# MCU64.net
KiCad netlist of a schematic drawn in Altium Designer
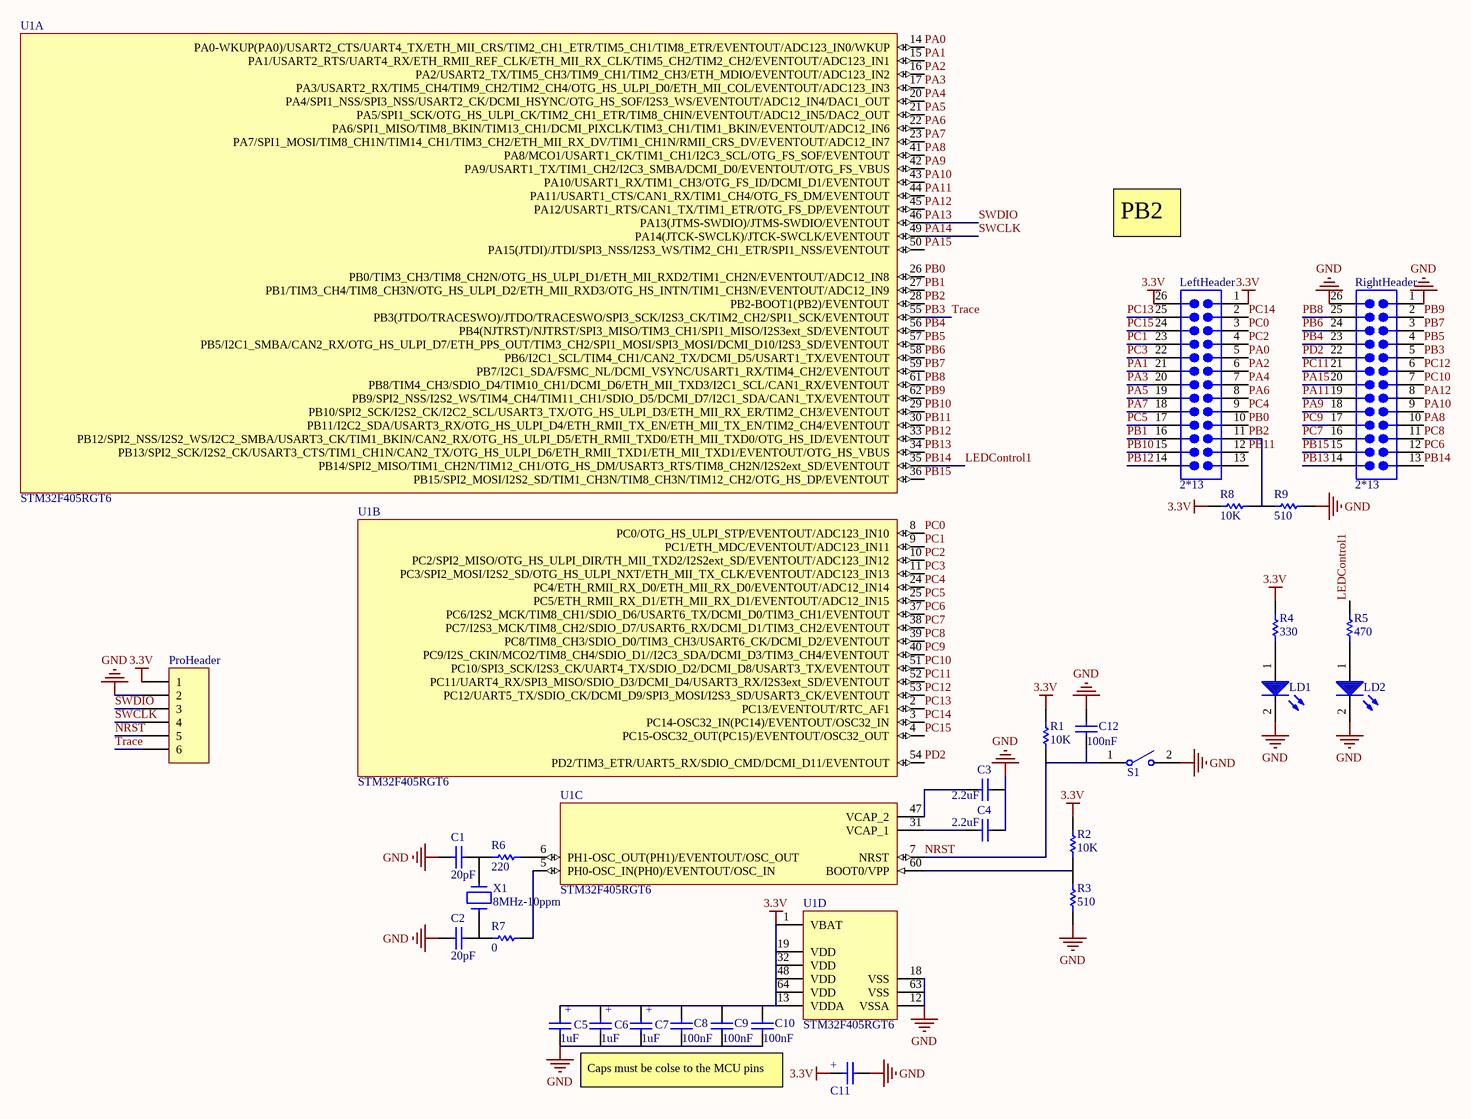
[diagram p0: MCU64.SchDoc]

(export (version "E")
  (design (tool "Eeschema 10.0.6"))
  (components
    (comp (ref "C1")
      (value "20pF")
      (footprint "SMD 805 CAP")
      (libsource (lib "Aryalib") (part "CAP without Pole"))
    )
    (comp (ref "C2")
      (value "20pF")
      (footprint "SMD 805 CAP")
      (libsource (lib "Aryalib") (part "CAP without Pole"))
    )
    (comp (ref "C3")
      (value "2.2uF")
      (footprint "SMD 805 CAP")
      (libsource (lib "Aryalib") (part "CAP without Pole"))
    )
    (comp (ref "C4")
      (value "2.2uF")
      (footprint "SMD 805 CAP")
      (libsource (lib "Aryalib") (part "CAP without Pole"))
    )
    (comp (ref "C5")
      (value "1uF")
      (footprint "MY_CAP_SMD-A")
      (description "3.2X1.6MM")
      (libsource (lib "AMINLIB") (part "CAP_TANTAL_A"))
    )
    (comp (ref "C6")
      (value "1uF")
      (footprint "MY_CAP_SMD-A")
      (description "3.2X1.6MM")
      (libsource (lib "AMINLIB") (part "CAP_TANTAL_A"))
    )
    (comp (ref "C7")
      (value "1uF")
      (footprint "MY_CAP_SMD-A")
      (description "3.2X1.6MM")
      (libsource (lib "AMINLIB") (part "CAP_TANTAL_A"))
    )
    (comp (ref "C8")
      (value "100nF")
      (footprint "SMD 805 CAP")
      (libsource (lib "Aryalib") (part "CAP without Pole"))
    )
    (comp (ref "C9")
      (value "100nF")
      (footprint "SMD 805 CAP")
      (libsource (lib "Aryalib") (part "CAP without Pole"))
    )
    (comp (ref "C10")
      (value "100nF")
      (footprint "SMD 805 CAP")
      (libsource (lib "Aryalib") (part "CAP without Pole"))
    )
    (comp (ref "C11")
      (value "Cap")
      (footprint "MY_CAP_SMD-D")
      (description "7.3X4.3MM")
      (libsource (lib "AMINLIB") (part "CAP_TANTAL_D"))
    )
    (comp (ref "C12")
      (value "100nF")
      (footprint "SMD 805 CAP")
      (libsource (lib "Aryalib") (part "CAP without Pole"))
    )
    (comp (ref "LD1")
      (value "150080BS75000")
      (footprint "LED_0805_Blue")
      (description "SMD mono-color Chip LED, WL-SMCW, Blue")
      (fields
        (field (name "MANUFACTURER") "W黵th Elektronik eiSos GmbH")
        (field (name "CREATED BY") "Christin Otto")
      )
      (libsource (lib "WL-SMCW_rev15b") (part "WL-SMCW 0805  150080BS75000"))
    )
    (comp (ref "LD2")
      (value "150080BS75000")
      (footprint "LED_0805_Blue")
      (description "SMD mono-color Chip LED, WL-SMCW, Blue")
      (fields
        (field (name "MANUFACTURER") "W黵th Elektronik eiSos GmbH")
        (field (name "CREATED BY") "Christin Otto")
      )
      (libsource (lib "WL-SMCW_rev15b") (part "WL-SMCW 0805  150080BS75000"))
    )
    (comp (ref "LeftHeader")
      (value "2*13")
      (footprint "61302621121")
      (description "WR-PHD 2.54 mm Dual Pin Header")
      (fields
        (field (name "MANUFACTURER") "Würth Elektronik eiSos GmbH")
        (field (name "PARTNO") "61302621121")
        (field (name "CREATED BY") "Karrer Zheng")
      )
      (libsource (lib "WE_WR-PHD_Pin Header_2.54mm_rev15c") (part "WE-2.54 mm Pin Header & Jumper 61302621121"))
    )
    (comp (ref "ProHeader")
      (value "WE-2.54 mm Pin Header & Jumper 61300611121")
      (footprint "61300611121")
      (description "WR-PHD 2.54mm Pin Header")
      (fields
        (field (name "MANUFACTURER") "Würth Elektronik eiSos GmbH")
        (field (name "PARTNO") "61300611121")
        (field (name "CREATED BY") "Karrer Zheng")
      )
      (libsource (lib "WE_WR-PHD_Pin Header_2.54mm_rev15c") (part "WE-2.54 mm Pin Header & Jumper 61300611121"))
    )
    (comp (ref "R1") (value "10K") (footprint "SMD 805") (libsource (lib "Aryalib") (part "Resistor")))
    (comp (ref "R2") (value "10K") (footprint "SMD 805") (libsource (lib "Aryalib") (part "Resistor")))
    (comp (ref "R3") (value "510") (footprint "SMD 805") (libsource (lib "Aryalib") (part "Resistor")))
    (comp (ref "R4") (value "330") (footprint "SMD 805") (libsource (lib "Aryalib") (part "Resistor")))
    (comp (ref "R5") (value "470") (footprint "SMD 805") (libsource (lib "Aryalib") (part "Resistor")))
    (comp (ref "R6") (value "220") (footprint "SMD 805") (libsource (lib "Aryalib") (part "Resistor")))
    (comp (ref "R7") (value "0") (footprint "SMD 805") (libsource (lib "Aryalib") (part "Resistor")))
    (comp (ref "R8") (value "10K") (footprint "SMD 805") (libsource (lib "Aryalib") (part "Resistor")))
    (comp (ref "R9") (value "510") (footprint "SMD 805") (libsource (lib "Aryalib") (part "Resistor")))
    (comp (ref "RightHeader")
      (value "2*13")
      (footprint "61302621121")
      (description "WR-PHD 2.54 mm Dual Pin Header")
      (fields
        (field (name "MANUFACTURER") "Würth Elektronik eiSos GmbH")
        (field (name "PARTNO") "61302621121")
        (field (name "CREATED BY") "Karrer Zheng")
      )
      (libsource (lib "WE_WR-PHD_Pin Header_2.54mm_rev15c") (part "WE-2.54 mm Pin Header & Jumper 61302621121"))
    )
    (comp (ref "S1")
      (value "Tact Switch")
      (footprint "4341x10438x6")
      (description "WS-TASV 6.0x3.5 mm SMD")
      (fields
        (field (name "PARTNO") "434111043826")
        (field (name "MANUFACTURER") "Wurth Elektronik")
        (field (name "CREATED BY") "Baojun Chen")
      )
      (libsource (lib "WS-TASV_rev15a") (part "WS-TASV, 434111043826"))
    )
    (comp (ref "U1")
      (value "STM32F405RGT6")
      (footprint "TQFP64_V")
      (libsource (lib "") (part "STM32F405RGT6_1"))
    )
    (comp (ref "X1")
      (value "8MHz-10ppm")
      (footprint "My_Crystal")
      (description "Crystal")
      (libsource (lib "AMINLIB") (part "CRYSTAL"))
    )
  )
  (nets
    (net (code "1") (name "/LEDControl1") (class "Default")
      (node (ref "R5") (pin "2") (pinfunction "2_2") (pintype "passive"))
      (node (ref "RightHeader") (pin "13") (pinfunction "13_13") (pintype "passive"))
      (node (ref "U1") (pin "35") (pinfunction "PB14/SPI2_MISO/TIM1_CH2N/TIM12_CH1/OTG_HS_DM/USART3_RTS/TIM8_CH2N/I2S2ext_SD/EVENTOUT_35") (pintype "bidirectional"))
    )
    (net (code "2") (name "/NRST") (class "Default")
      (node (ref "C12") (pin "1") (pinfunction "1_1") (pintype "passive"))
      (node (ref "ProHeader") (pin "5") (pinfunction "5_5") (pintype "passive"))
      (node (ref "R1") (pin "1") (pinfunction "1_1") (pintype "passive"))
      (node (ref "S1") (pin "1") (pinfunction "1_1") (pintype "passive"))
      (node (ref "U1") (pin "7") (pinfunction "NRST_7") (pintype "bidirectional"))
    )
    (net (code "3") (name "/PA0") (class "Default")
      (node (ref "LeftHeader") (pin "5") (pinfunction "5_5") (pintype "passive"))
      (node (ref "U1") (pin "14") (pinfunction "PA0-WKUP(PA0)/USART2_CTS/UART4_TX/ETH_MII_CRS/TIM2_CH1_ETR/TIM5_CH1/TIM8_ETR/EVENTOUT/ADC123_IN0/WKUP_14") (pintype "bidirectional"))
    )
    (net (code "4") (name "/PA1") (class "Default")
      (node (ref "LeftHeader") (pin "21") (pinfunction "21_21") (pintype "passive"))
      (node (ref "U1") (pin "15") (pinfunction "PA1/USART2_RTS/UART4_RX/ETH_RMII_REF_CLK/ETH_MII_RX_CLK/TIM5_CH2/TIM2_CH2/EVENTOUT/ADC123_IN1_15") (pintype "bidirectional"))
    )
    (net (code "5") (name "/PA2") (class "Default")
      (node (ref "LeftHeader") (pin "6") (pinfunction "6_6") (pintype "passive"))
      (node (ref "U1") (pin "16") (pinfunction "PA2/USART2_TX/TIM5_CH3/TIM9_CH1/TIM2_CH3/ETH_MDIO/EVENTOUT/ADC123_IN2_16") (pintype "bidirectional"))
    )
    (net (code "6") (name "/PA3") (class "Default")
      (node (ref "LeftHeader") (pin "20") (pinfunction "20_20") (pintype "passive"))
      (node (ref "U1") (pin "17") (pinfunction "PA3/USART2_RX/TIM5_CH4/TIM9_CH2/TIM2_CH4/OTG_HS_ULPI_D0/ETH_MII_COL/EVENTOUT/ADC123_IN3_17") (pintype "bidirectional"))
    )
    (net (code "7") (name "/PA4") (class "Default")
      (node (ref "LeftHeader") (pin "7") (pinfunction "7_7") (pintype "passive"))
      (node (ref "U1") (pin "20") (pinfunction "PA4/SPI1_NSS/SPI3_NSS/USART2_CK/DCMI_HSYNC/OTG_HS_SOF/I2S3_WS/EVENTOUT/ADC12_IN4/DAC1_OUT_20") (pintype "bidirectional"))
    )
    (net (code "8") (name "/PA5") (class "Default")
      (node (ref "LeftHeader") (pin "19") (pinfunction "19_19") (pintype "passive"))
      (node (ref "U1") (pin "21") (pinfunction "PA5/SPI1_SCK/OTG_HS_ULPI_CK/TIM2_CH1_ETR/TIM8_CHIN/EVENTOUT/ADC12_IN5/DAC2_OUT_21") (pintype "bidirectional"))
    )
    (net (code "9") (name "/PA6") (class "Default")
      (node (ref "LeftHeader") (pin "8") (pinfunction "8_8") (pintype "passive"))
      (node (ref "U1") (pin "22") (pinfunction "PA6/SPI1_MISO/TIM8_BKIN/TIM13_CH1/DCMI_PIXCLK/TIM3_CH1/TIM1_BKIN/EVENTOUT/ADC12_IN6_22") (pintype "bidirectional"))
    )
    (net (code "10") (name "/PA7") (class "Default")
      (node (ref "LeftHeader") (pin "18") (pinfunction "18_18") (pintype "passive"))
      (node (ref "U1") (pin "23") (pinfunction "PA7/SPI1_MOSI/TIM8_CH1N/TIM14_CH1/TIM3_CH2/ETH_MII_RX_DV/TIM1_CH1N/RMII_CRS_DV/EVENTOUT/ADC12_IN7_23") (pintype "bidirectional"))
    )
    (net (code "11") (name "/PA8") (class "Default")
      (node (ref "RightHeader") (pin "10") (pinfunction "10_10") (pintype "passive"))
      (node (ref "U1") (pin "41") (pinfunction "PA8/MCO1/USART1_CK/TIM1_CH1/I2C3_SCL/OTG_FS_SOF/EVENTOUT_41") (pintype "bidirectional"))
    )
    (net (code "12") (name "/PA9") (class "Default")
      (node (ref "RightHeader") (pin "18") (pinfunction "18_18") (pintype "passive"))
      (node (ref "U1") (pin "42") (pinfunction "PA9/USART1_TX/TIM1_CH2/I2C3_SMBA/DCMI_D0/EVENTOUT/OTG_FS_VBUS_42") (pintype "bidirectional"))
    )
    (net (code "13") (name "/PA10") (class "Default")
      (node (ref "RightHeader") (pin "9") (pinfunction "9_9") (pintype "passive"))
      (node (ref "U1") (pin "43") (pinfunction "PA10/USART1_RX/TIM1_CH3/OTG_FS_ID/DCMI_D1/EVENTOUT_43") (pintype "bidirectional"))
    )
    (net (code "14") (name "/PA11") (class "Default")
      (node (ref "RightHeader") (pin "19") (pinfunction "19_19") (pintype "passive"))
      (node (ref "U1") (pin "44") (pinfunction "PA11/USART1_CTS/CAN1_RX/TIM1_CH4/OTG_FS_DM/EVENTOUT_44") (pintype "bidirectional"))
    )
    (net (code "15") (name "/PA12") (class "Default")
      (node (ref "RightHeader") (pin "8") (pinfunction "8_8") (pintype "passive"))
      (node (ref "U1") (pin "45") (pinfunction "PA12/USART1_RTS/CAN1_TX/TIM1_ETR/OTG_FS_DP/EVENTOUT_45") (pintype "bidirectional"))
    )
    (net (code "16") (name "/PA13") (class "Default")
      (node (ref "ProHeader") (pin "3") (pinfunction "3_3") (pintype "passive"))
      (node (ref "U1") (pin "46") (pinfunction "PA13(JTMS-SWDIO)/JTMS-SWDIO/EVENTOUT_46") (pintype "bidirectional"))
    )
    (net (code "17") (name "/PA14") (class "Default")
      (node (ref "ProHeader") (pin "4") (pinfunction "4_4") (pintype "passive"))
      (node (ref "U1") (pin "49") (pinfunction "PA14(JTCK-SWCLK)/JTCK-SWCLK/EVENTOUT_49") (pintype "bidirectional"))
    )
    (net (code "18") (name "/PA15") (class "Default")
      (node (ref "RightHeader") (pin "20") (pinfunction "20_20") (pintype "passive"))
      (node (ref "U1") (pin "50") (pinfunction "PA15(JTDI)/JTDI/SPI3_NSS/I2S3_WS/TIM2_CH1_ETR/SPI1_NSS/EVENTOUT_50") (pintype "bidirectional"))
    )
    (net (code "19") (name "/PB0") (class "Default")
      (node (ref "LeftHeader") (pin "10") (pinfunction "10_10") (pintype "passive"))
      (node (ref "U1") (pin "26") (pinfunction "PB0/TIM3_CH3/TIM8_CH2N/OTG_HS_ULPI_D1/ETH_MII_RXD2/TIM1_CH2N/EVENTOUT/ADC12_IN8_26") (pintype "bidirectional"))
    )
    (net (code "20") (name "/PB1") (class "Default")
      (node (ref "LeftHeader") (pin "16") (pinfunction "16_16") (pintype "passive"))
      (node (ref "U1") (pin "27") (pinfunction "PB1/TIM3_CH4/TIM8_CH3N/OTG_HS_ULPI_D2/ETH_MII_RXD3/OTG_HS_INTN/TIM1_CH3N/EVENTOUT/ADC12_IN9_27") (pintype "bidirectional"))
    )
    (net (code "21") (name "/PB2") (class "Default")
      (node (ref "LeftHeader") (pin "11") (pinfunction "11_11") (pintype "passive"))
      (node (ref "R8") (pin "1") (pinfunction "1_1") (pintype "passive"))
      (node (ref "R9") (pin "2") (pinfunction "2_2") (pintype "passive"))
      (node (ref "U1") (pin "28") (pinfunction "PB2-BOOT1(PB2)/EVENTOUT_28") (pintype "bidirectional"))
    )
    (net (code "22") (name "/PB3") (class "Default")
      (node (ref "ProHeader") (pin "6") (pinfunction "6_6") (pintype "passive"))
      (node (ref "RightHeader") (pin "5") (pinfunction "5_5") (pintype "passive"))
      (node (ref "U1") (pin "55") (pinfunction "PB3(JTDO/TRACESWO)/JTDO/TRACESWO/SPI3_SCK/I2S3_CK/TIM2_CH2/SPI1_SCK/EVENTOUT_55") (pintype "bidirectional"))
    )
    (net (code "23") (name "/PB4") (class "Default")
      (node (ref "RightHeader") (pin "23") (pinfunction "23_23") (pintype "passive"))
      (node (ref "U1") (pin "56") (pinfunction "PB4(NJTRST)/NJTRST/SPI3_MISO/TIM3_CH1/SPI1_MISO/I2S3ext_SD/EVENTOUT_56") (pintype "bidirectional"))
    )
    (net (code "24") (name "/PB5") (class "Default")
      (node (ref "RightHeader") (pin "4") (pinfunction "4_4") (pintype "passive"))
      (node (ref "U1") (pin "57") (pinfunction "PB5/I2C1_SMBA/CAN2_RX/OTG_HS_ULPI_D7/ETH_PPS_OUT/TIM3_CH2/SPI1_MOSI/SPI3_MOSI/DCMI_D10/I2S3_SD/EVENTOUT_57") (pintype "bidirectional"))
    )
    (net (code "25") (name "/PB6") (class "Default")
      (node (ref "RightHeader") (pin "24") (pinfunction "24_24") (pintype "passive"))
      (node (ref "U1") (pin "58") (pinfunction "PB6/I2C1_SCL/TIM4_CH1/CAN2_TX/DCMI_D5/USART1_TX/EVENTOUT_58") (pintype "bidirectional"))
    )
    (net (code "26") (name "/PB7") (class "Default")
      (node (ref "RightHeader") (pin "3") (pinfunction "3_3") (pintype "passive"))
      (node (ref "U1") (pin "59") (pinfunction "PB7/I2C1_SDA/FSMC_NL/DCMI_VSYNC/USART1_RX/TIM4_CH2/EVENTOUT_59") (pintype "bidirectional"))
    )
    (net (code "27") (name "/PB8") (class "Default")
      (node (ref "RightHeader") (pin "25") (pinfunction "25_25") (pintype "passive"))
      (node (ref "U1") (pin "61") (pinfunction "PB8/TIM4_CH3/SDIO_D4/TIM10_CH1/DCMI_D6/ETH_MII_TXD3/I2C1_SCL/CAN1_RX/EVENTOUT_61") (pintype "bidirectional"))
    )
    (net (code "28") (name "/PB9") (class "Default")
      (node (ref "RightHeader") (pin "2") (pinfunction "2_2") (pintype "passive"))
      (node (ref "U1") (pin "62") (pinfunction "PB9/SPI2_NSS/I2S2_WS/TIM4_CH4/TIM11_CH1/SDIO_D5/DCMI_D7/I2C1_SDA/CAN1_TX/EVENTOUT_62") (pintype "bidirectional"))
    )
    (net (code "29") (name "/PB10") (class "Default")
      (node (ref "LeftHeader") (pin "15") (pinfunction "15_15") (pintype "passive"))
      (node (ref "U1") (pin "29") (pinfunction "PB10/SPI2_SCK/I2S2_CK/I2C2_SCL/USART3_TX/OTG_HS_ULPI_D3/ETH_MII_RX_ER/TIM2_CH3/EVENTOUT_29") (pintype "bidirectional"))
    )
    (net (code "30") (name "/PB11") (class "Default")
      (node (ref "LeftHeader") (pin "12") (pinfunction "12_12") (pintype "passive"))
      (node (ref "U1") (pin "30") (pinfunction "PB11/I2C2_SDA/USART3_RX/OTG_HS_ULPI_D4/ETH_RMII_TX_EN/ETH_MII_TX_EN/TIM2_CH4/EVENTOUT_30") (pintype "bidirectional"))
    )
    (net (code "31") (name "/PB12") (class "Default")
      (node (ref "LeftHeader") (pin "14") (pinfunction "14_14") (pintype "passive"))
      (node (ref "U1") (pin "33") (pinfunction "PB12/SPI2_NSS/I2S2_WS/I2C2_SMBA/USART3_CK/TIM1_BKIN/CAN2_RX/OTG_HS_ULPI_D5/ETH_RMII_TXD0/ETH_MII_TXD0/OTG_HS_ID/EVENTOUT_33") (pintype "bidirectional"))
    )
    (net (code "32") (name "/PB13") (class "Default")
      (node (ref "RightHeader") (pin "14") (pinfunction "14_14") (pintype "passive"))
      (node (ref "U1") (pin "34") (pinfunction "PB13/SPI2_SCK/I2S2_CK/USART3_CTS/TIM1_CH1N/CAN2_TX/OTG_HS_ULPI_D6/ETH_RMII_TXD1/ETH_MII_TXD1/EVENTOUT/OTG_HS_VBUS_34") (pintype "bidirectional"))
    )
    (net (code "33") (name "/PB15") (class "Default")
      (node (ref "RightHeader") (pin "15") (pinfunction "15_15") (pintype "passive"))
      (node (ref "U1") (pin "36") (pinfunction "PB15/SPI2_MOSI/I2S2_SD/TIM1_CH3N/TIM8_CH3N/TIM12_CH2/OTG_HS_DP/EVENTOUT_36") (pintype "bidirectional"))
    )
    (net (code "34") (name "/PC0") (class "Default")
      (node (ref "LeftHeader") (pin "3") (pinfunction "3_3") (pintype "passive"))
      (node (ref "U1") (pin "8") (pinfunction "PC0/OTG_HS_ULPI_STP/EVENTOUT/ADC123_IN10_8") (pintype "bidirectional"))
    )
    (net (code "35") (name "/PC1") (class "Default")
      (node (ref "LeftHeader") (pin "23") (pinfunction "23_23") (pintype "passive"))
      (node (ref "U1") (pin "9") (pinfunction "PC1/ETH_MDC/EVENTOUT/ADC123_IN11_9") (pintype "bidirectional"))
    )
    (net (code "36") (name "/PC2") (class "Default")
      (node (ref "LeftHeader") (pin "4") (pinfunction "4_4") (pintype "passive"))
      (node (ref "U1") (pin "10") (pinfunction "PC2/SPI2_MISO/OTG_HS_ULPI_DIR/TH_MII_TXD2/I2S2ext_SD/EVENTOUT/ADC123_IN12_10") (pintype "bidirectional"))
    )
    (net (code "37") (name "/PC3") (class "Default")
      (node (ref "LeftHeader") (pin "22") (pinfunction "22_22") (pintype "passive"))
      (node (ref "U1") (pin "11") (pinfunction "PC3/SPI2_MOSI/I2S2_SD/OTG_HS_ULPI_NXT/ETH_MII_TX_CLK/EVENTOUT/ADC123_IN13_11") (pintype "bidirectional"))
    )
    (net (code "38") (name "/PC4") (class "Default")
      (node (ref "LeftHeader") (pin "9") (pinfunction "9_9") (pintype "passive"))
      (node (ref "U1") (pin "24") (pinfunction "PC4/ETH_RMII_RX_D0/ETH_MII_RX_D0/EVENTOUT/ADC12_IN14_24") (pintype "bidirectional"))
    )
    (net (code "39") (name "/PC5") (class "Default")
      (node (ref "LeftHeader") (pin "17") (pinfunction "17_17") (pintype "passive"))
      (node (ref "U1") (pin "25") (pinfunction "PC5/ETH_RMII_RX_D1/ETH_MII_RX_D1/EVENTOUT/ADC12_IN15_25") (pintype "bidirectional"))
    )
    (net (code "40") (name "/PC6") (class "Default")
      (node (ref "RightHeader") (pin "12") (pinfunction "12_12") (pintype "passive"))
      (node (ref "U1") (pin "37") (pinfunction "PC6/I2S2_MCK/TIM8_CH1/SDIO_D6/USART6_TX/DCMI_D0/TIM3_CH1/EVENTOUT_37") (pintype "bidirectional"))
    )
    (net (code "41") (name "/PC7") (class "Default")
      (node (ref "RightHeader") (pin "16") (pinfunction "16_16") (pintype "passive"))
      (node (ref "U1") (pin "38") (pinfunction "PC7/I2S3_MCK/TIM8_CH2/SDIO_D7/USART6_RX/DCMI_D1/TIM3_CH2/EVENTOUT_38") (pintype "bidirectional"))
    )
    (net (code "42") (name "/PC8") (class "Default")
      (node (ref "RightHeader") (pin "11") (pinfunction "11_11") (pintype "passive"))
      (node (ref "U1") (pin "39") (pinfunction "PC8/TIM8_CH3/SDIO_D0/TIM3_CH3/USART6_CK/DCMI_D2/EVENTOUT_39") (pintype "bidirectional"))
    )
    (net (code "43") (name "/PC9") (class "Default")
      (node (ref "RightHeader") (pin "17") (pinfunction "17_17") (pintype "passive"))
      (node (ref "U1") (pin "40") (pinfunction "PC9/I2S_CKIN/MCO2/TIM8_CH4/SDIO_D1//I2C3_SDA/DCMI_D3/TIM3_CH4/EVENTOUT_40") (pintype "bidirectional"))
    )
    (net (code "44") (name "/PC10") (class "Default")
      (node (ref "RightHeader") (pin "7") (pinfunction "7_7") (pintype "passive"))
      (node (ref "U1") (pin "51") (pinfunction "PC10/SPI3_SCK/I2S3_CK/UART4_TX/SDIO_D2/DCMI_D8/USART3_TX/EVENTOUT_51") (pintype "bidirectional"))
    )
    (net (code "45") (name "/PC11") (class "Default")
      (node (ref "RightHeader") (pin "21") (pinfunction "21_21") (pintype "passive"))
      (node (ref "U1") (pin "52") (pinfunction "PC11/UART4_RX/SPI3_MISO/SDIO_D3/DCMI_D4/USART3_RX/I2S3ext_SD/EVENTOUT_52") (pintype "bidirectional"))
    )
    (net (code "46") (name "/PC12") (class "Default")
      (node (ref "RightHeader") (pin "6") (pinfunction "6_6") (pintype "passive"))
      (node (ref "U1") (pin "53") (pinfunction "PC12/UART5_TX/SDIO_CK/DCMI_D9/SPI3_MOSI/I2S3_SD/USART3_CK/EVENTOUT_53") (pintype "bidirectional"))
    )
    (net (code "47") (name "/PC13") (class "Default")
      (node (ref "LeftHeader") (pin "25") (pinfunction "25_25") (pintype "passive"))
      (node (ref "U1") (pin "2") (pinfunction "PC13/EVENTOUT/RTC_AF1_2") (pintype "bidirectional"))
    )
    (net (code "48") (name "/PC14") (class "Default")
      (node (ref "LeftHeader") (pin "2") (pinfunction "2_2") (pintype "passive"))
      (node (ref "U1") (pin "3") (pinfunction "PC14-OSC32_IN(PC14)/EVENTOUT/OSC32_IN_3") (pintype "bidirectional"))
    )
    (net (code "49") (name "/PC15") (class "Default")
      (node (ref "LeftHeader") (pin "24") (pinfunction "24_24") (pintype "passive"))
      (node (ref "U1") (pin "4") (pinfunction "PC15-OSC32_OUT(PC15)/EVENTOUT/OSC32_OUT_4") (pintype "bidirectional"))
    )
    (net (code "50") (name "/PD2") (class "Default")
      (node (ref "RightHeader") (pin "22") (pinfunction "22_22") (pintype "passive"))
      (node (ref "U1") (pin "54") (pinfunction "PD2/TIM3_ETR/UART5_RX/SDIO_CMD/DCMI_D11/EVENTOUT_54") (pintype "bidirectional"))
    )
    (net (code "51") (name "3.3V") (class "Default")
      (node (ref "C10") (pin "2") (pinfunction "2_2") (pintype "passive"))
      (node (ref "C11") (pin "+") (pinfunction "+_+") (pintype "passive"))
      (node (ref "C5") (pin "+") (pinfunction "+_+") (pintype "passive"))
      (node (ref "C6") (pin "+") (pinfunction "+_+") (pintype "passive"))
      (node (ref "C7") (pin "+") (pinfunction "+_+") (pintype "passive"))
      (node (ref "C8") (pin "2") (pinfunction "2_2") (pintype "passive"))
      (node (ref "C9") (pin "2") (pinfunction "2_2") (pintype "passive"))
      (node (ref "LeftHeader") (pin "1") (pinfunction "1_1") (pintype "passive"))
      (node (ref "LeftHeader") (pin "26") (pinfunction "26_26") (pintype "passive"))
      (node (ref "ProHeader") (pin "1") (pinfunction "1_1") (pintype "passive"))
      (node (ref "R1") (pin "2") (pinfunction "2_2") (pintype "passive"))
      (node (ref "R2") (pin "2") (pinfunction "2_2") (pintype "passive"))
      (node (ref "R4") (pin "2") (pinfunction "2_2") (pintype "passive"))
      (node (ref "R8") (pin "2") (pinfunction "2_2") (pintype "passive"))
      (node (ref "U1") (pin "1") (pinfunction "VBAT_1") (pintype "power_in"))
      (node (ref "U1") (pin "13") (pinfunction "VDDA_13") (pintype "power_in"))
      (node (ref "U1") (pin "19") (pinfunction "VDD_19") (pintype "power_in"))
      (node (ref "U1") (pin "32") (pinfunction "VDD_32") (pintype "power_in"))
      (node (ref "U1") (pin "48") (pinfunction "VDD_48") (pintype "power_in"))
      (node (ref "U1") (pin "64") (pinfunction "VDD_64") (pintype "power_in"))
    )
    (net (code "52") (name "GND") (class "Default")
      (node (ref "C1") (pin "1") (pinfunction "1_1") (pintype "passive"))
      (node (ref "C10") (pin "1") (pinfunction "1_1") (pintype "passive"))
      (node (ref "C11") (pin "-") (pinfunction "-_-") (pintype "passive"))
      (node (ref "C12") (pin "2") (pinfunction "2_2") (pintype "passive"))
      (node (ref "C2") (pin "1") (pinfunction "1_1") (pintype "passive"))
      (node (ref "C3") (pin "2") (pinfunction "2_2") (pintype "passive"))
      (node (ref "C4") (pin "2") (pinfunction "2_2") (pintype "passive"))
      (node (ref "C5") (pin "-") (pinfunction "-_-") (pintype "passive"))
      (node (ref "C6") (pin "-") (pinfunction "-_-") (pintype "passive"))
      (node (ref "C7") (pin "-") (pinfunction "-_-") (pintype "passive"))
      (node (ref "C8") (pin "1") (pinfunction "1_1") (pintype "passive"))
      (node (ref "C9") (pin "1") (pinfunction "1_1") (pintype "passive"))
      (node (ref "LD1") (pin "2") (pinfunction "C_2") (pintype "passive"))
      (node (ref "LD2") (pin "2") (pinfunction "C_2") (pintype "passive"))
      (node (ref "ProHeader") (pin "2") (pinfunction "2_2") (pintype "passive"))
      (node (ref "R3") (pin "1") (pinfunction "1_1") (pintype "passive"))
      (node (ref "R9") (pin "1") (pinfunction "1_1") (pintype "passive"))
      (node (ref "RightHeader") (pin "1") (pinfunction "1_1") (pintype "passive"))
      (node (ref "RightHeader") (pin "26") (pinfunction "26_26") (pintype "passive"))
      (node (ref "S1") (pin "2") (pinfunction "2_2") (pintype "passive"))
      (node (ref "U1") (pin "12") (pinfunction "VSSA_12") (pintype "power_in"))
      (node (ref "U1") (pin "18") (pinfunction "VSS_18") (pintype "power_in"))
      (node (ref "U1") (pin "63") (pinfunction "VSS_63") (pintype "power_in"))
    )
    (net (code "53") (name "Net-(C1-Pad2)") (class "Default")
      (node (ref "C1") (pin "2") (pinfunction "2_2") (pintype "passive"))
      (node (ref "R6") (pin "1") (pinfunction "1_1") (pintype "passive"))
      (node (ref "X1") (pin "2") (pinfunction "2_2") (pintype "passive"))
    )
    (net (code "54") (name "Net-(C2-Pad2)") (class "Default")
      (node (ref "C2") (pin "2") (pinfunction "2_2") (pintype "passive"))
      (node (ref "R7") (pin "1") (pinfunction "1_1") (pintype "passive"))
      (node (ref "X1") (pin "1") (pinfunction "1_1") (pintype "passive"))
    )
    (net (code "55") (name "Net-(LD1-A)") (class "Default")
      (node (ref "LD1") (pin "1") (pinfunction "A_1") (pintype "passive"))
      (node (ref "R4") (pin "1") (pinfunction "1_1") (pintype "passive"))
    )
    (net (code "56") (name "Net-(LD2-A)") (class "Default")
      (node (ref "LD2") (pin "1") (pinfunction "A_1") (pintype "passive"))
      (node (ref "R5") (pin "1") (pinfunction "1_1") (pintype "passive"))
    )
    (net (code "57") (name "Net-(U1C-BOOT0{slash}VPP)") (class "Default")
      (node (ref "R2") (pin "1") (pinfunction "1_1") (pintype "passive"))
      (node (ref "R3") (pin "2") (pinfunction "2_2") (pintype "passive"))
      (node (ref "U1") (pin "60") (pinfunction "BOOT0/VPP_60") (pintype "input"))
    )
    (net (code "58") (name "Net-(U1C-PH0-OSC_IN(PH0){slash}EVENTOUT{slash}OSC_IN)") (class "Default")
      (node (ref "R7") (pin "2") (pinfunction "2_2") (pintype "passive"))
      (node (ref "U1") (pin "5") (pinfunction "PH0-OSC_IN(PH0)/EVENTOUT/OSC_IN_5") (pintype "bidirectional"))
    )
    (net (code "59") (name "Net-(U1C-PH1-OSC_OUT(PH1){slash}EVENTOUT{slash}OSC_OUT)") (class "Default")
      (node (ref "R6") (pin "2") (pinfunction "2_2") (pintype "passive"))
      (node (ref "U1") (pin "6") (pinfunction "PH1-OSC_OUT(PH1)/EVENTOUT/OSC_OUT_6") (pintype "bidirectional"))
    )
    (net (code "60") (name "Net-(U1C-VCAP_1)") (class "Default")
      (node (ref "C4") (pin "1") (pinfunction "1_1") (pintype "passive"))
      (node (ref "U1") (pin "31") (pinfunction "VCAP_1_31") (pintype "power_in"))
    )
    (net (code "61") (name "Net-(U1C-VCAP_2)") (class "Default")
      (node (ref "C3") (pin "1") (pinfunction "1_1") (pintype "passive"))
      (node (ref "U1") (pin "47") (pinfunction "VCAP_2_47") (pintype "power_in"))
    )
    (net (code "62") (name "unconnected-(LeftHeader-Pad13)") (class "Default")
      (node (ref "LeftHeader") (pin "13") (pinfunction "13_13") (pintype "passive"))
    )
  )
)
